# hail.net
KiCad netlist of a schematic drawn in EAGLE
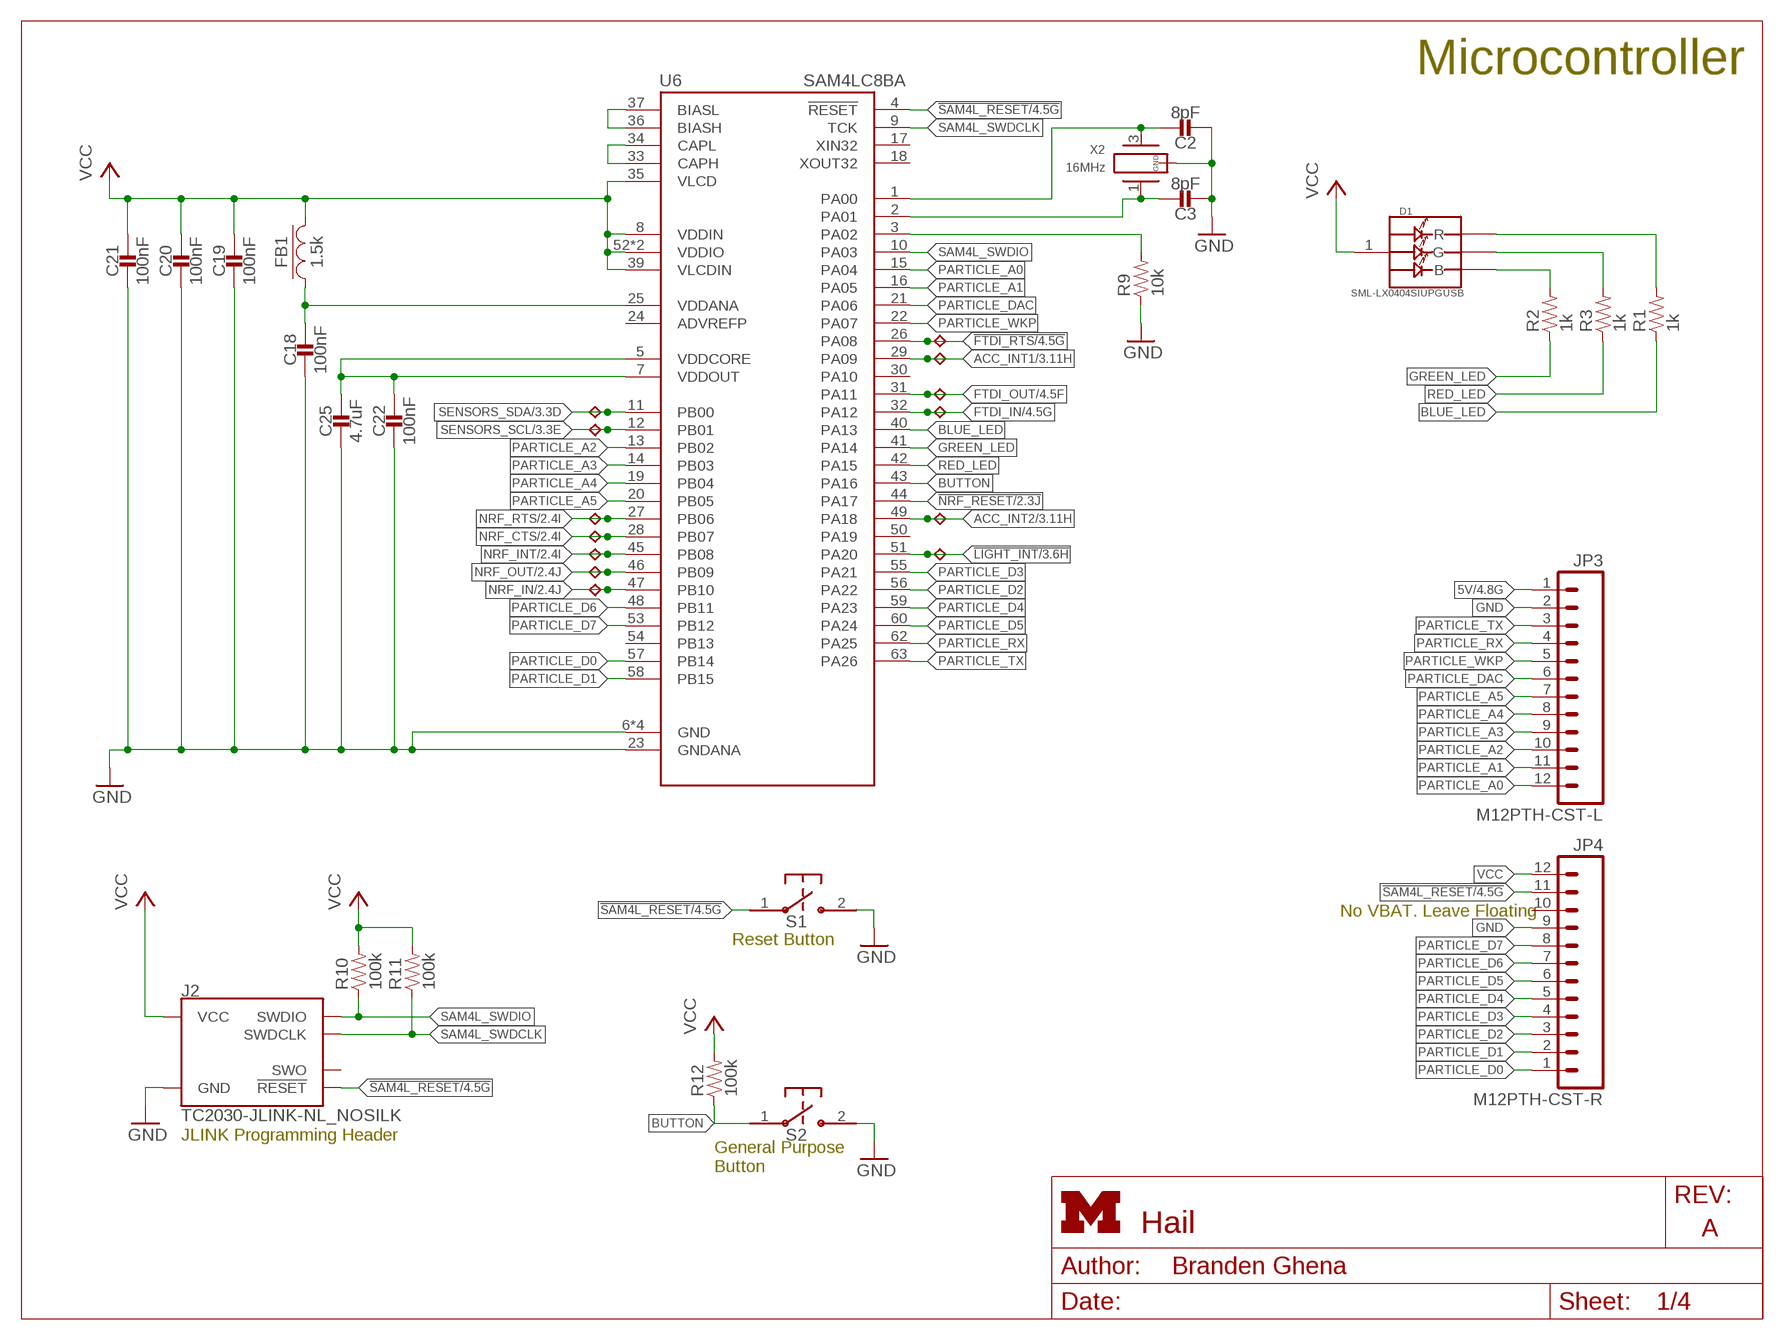
[diagram p0: schematic, sheet 1]
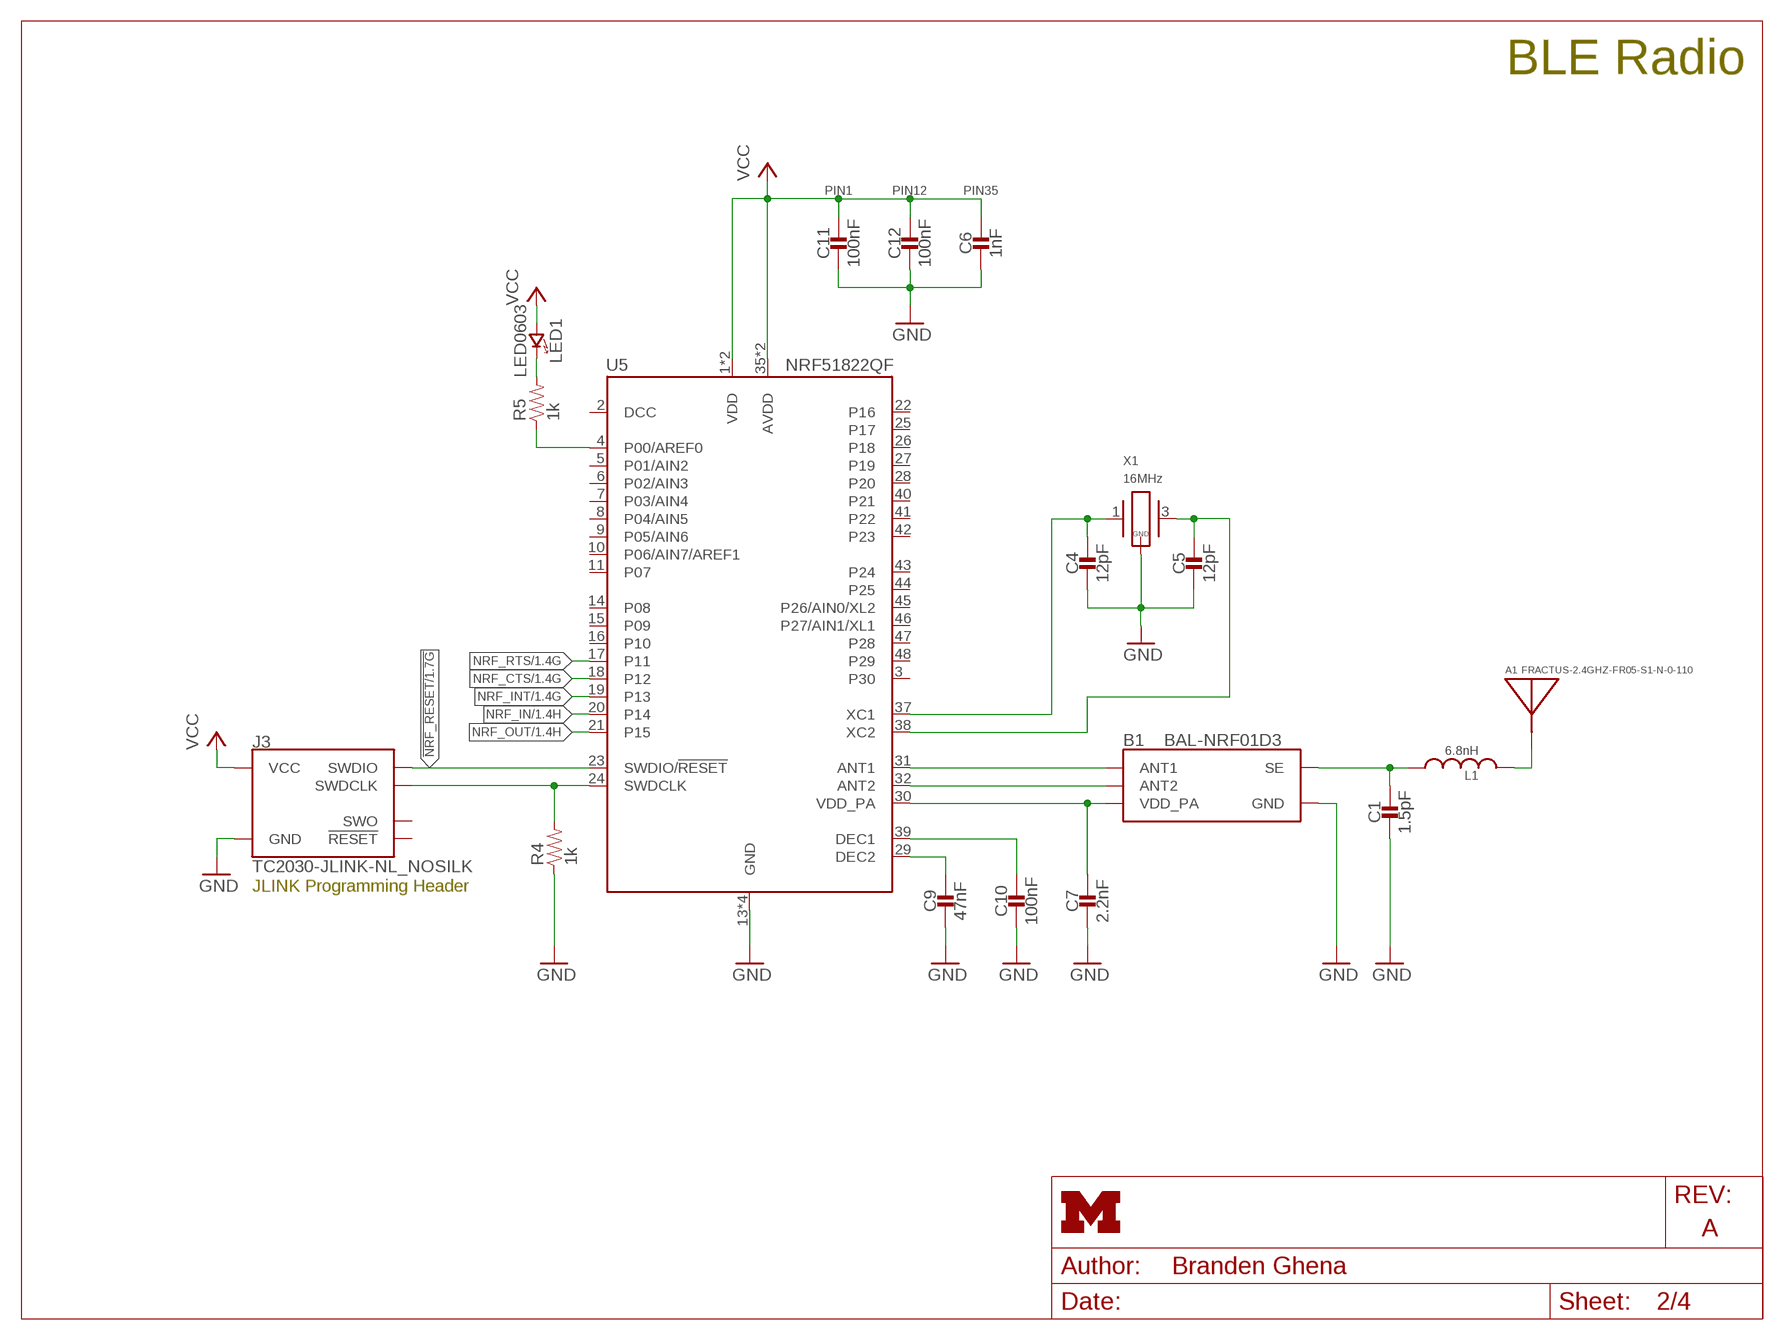
[diagram p1: schematic, sheet 2]
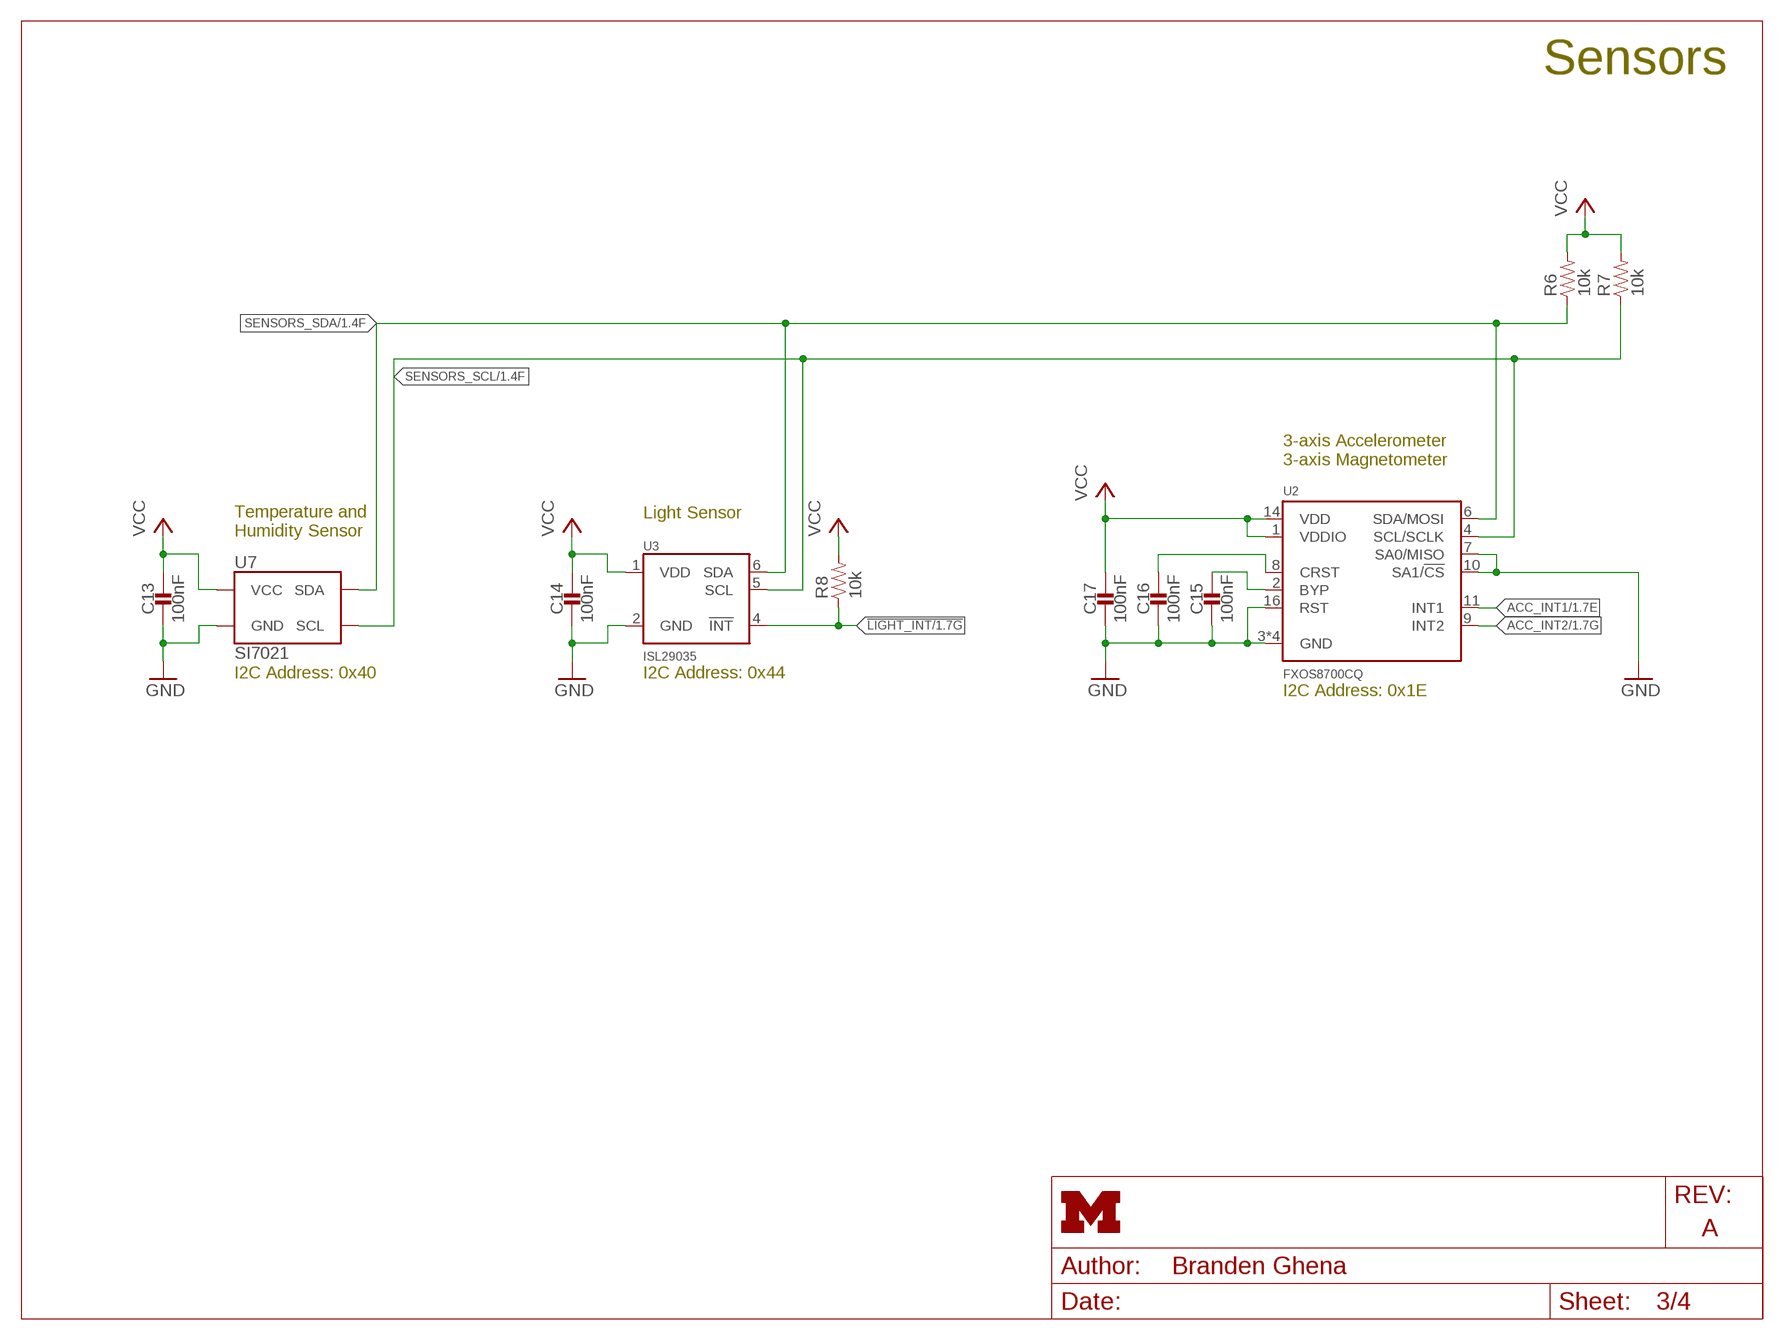
[diagram p2: schematic, sheet 3]
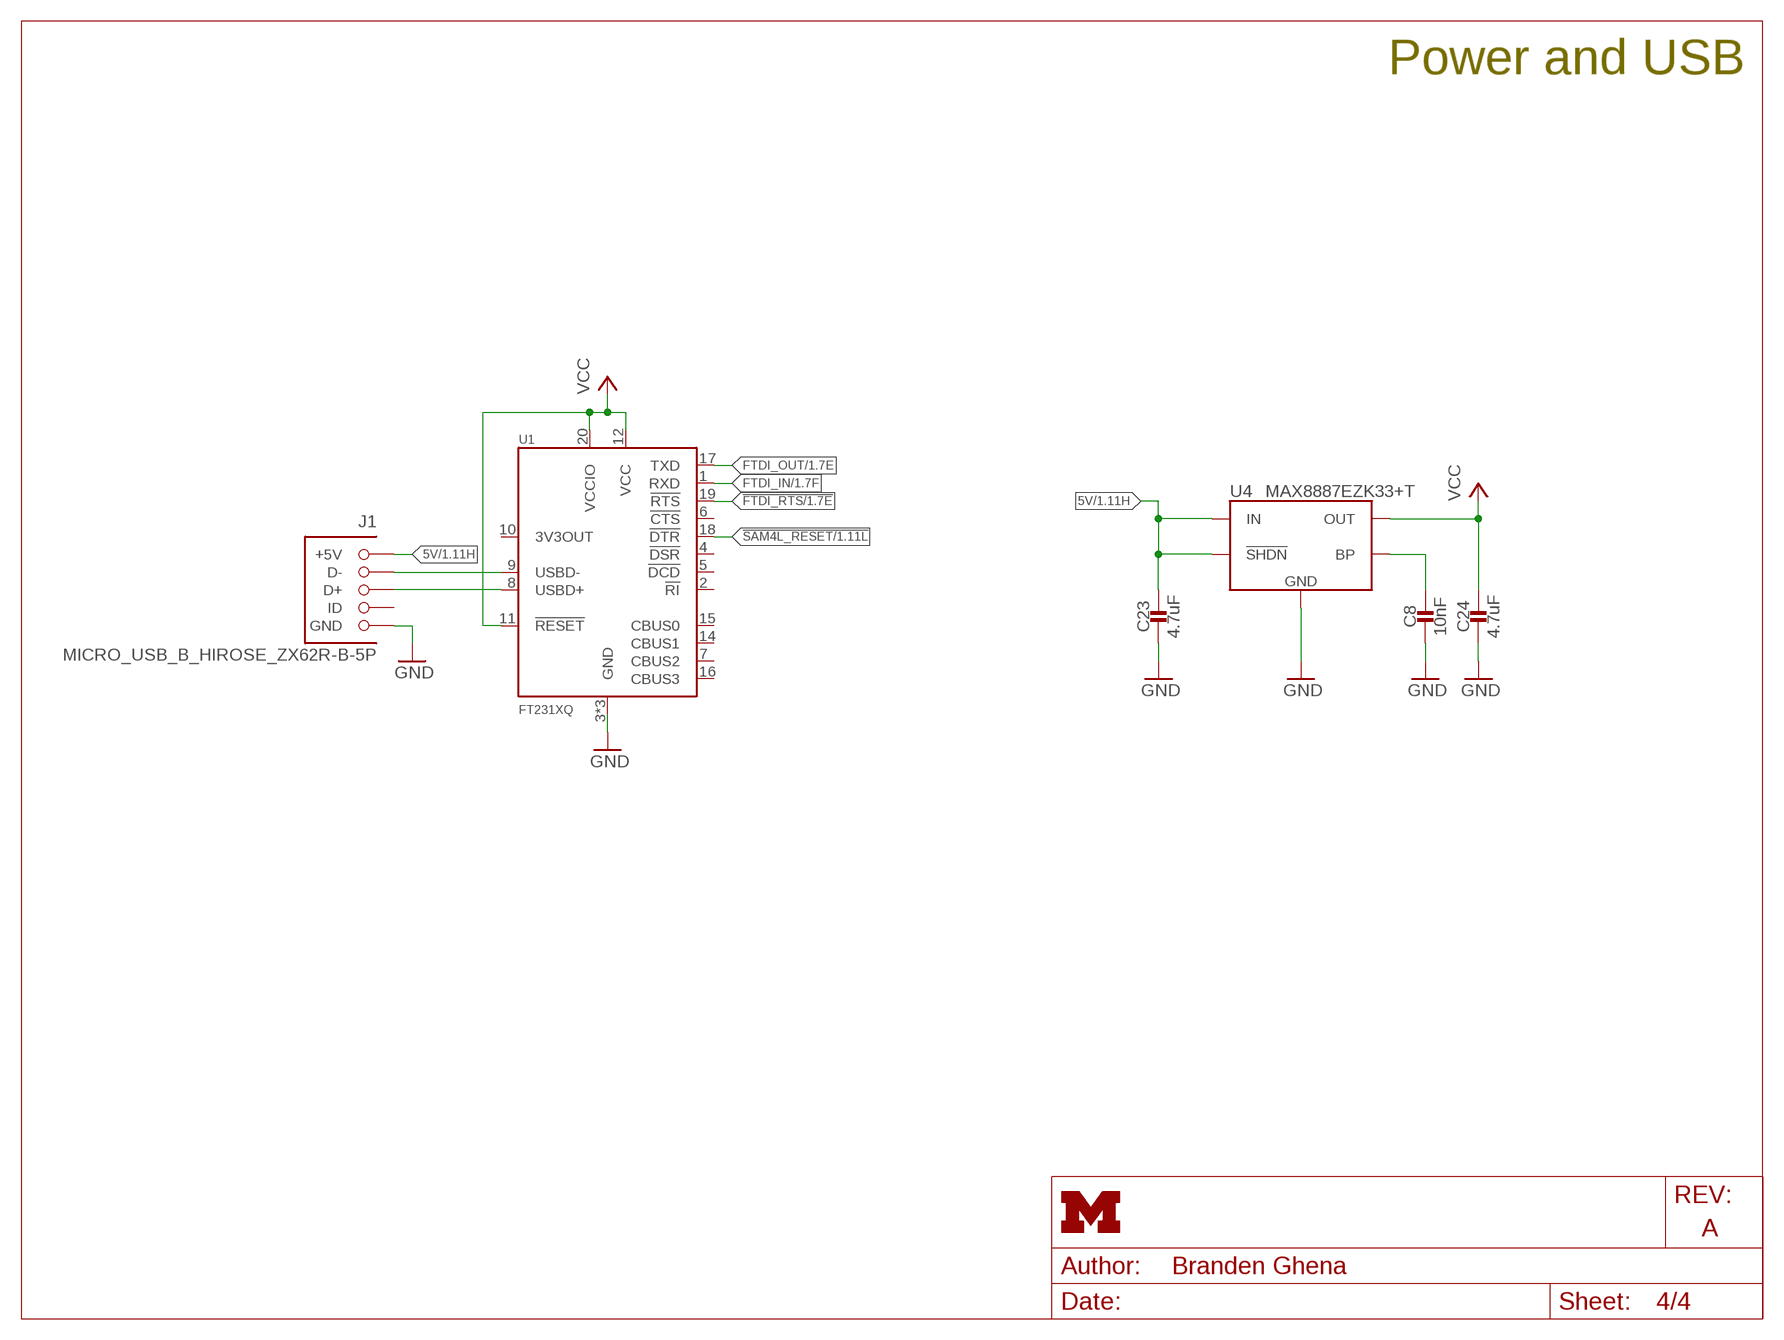
[diagram p3: schematic, sheet 4]

(export (version "E")
  (design (tool "Eeschema 10.0.6"))
  (components
    (comp (ref "A1")
      (value "FRACTUS-2.4GHZ-FR05-S1-N-0-110")
      (footprint "eagle-import:FRACTUS-ANTENNA-FR05-S1-N-0-110")
      (libsource (lib "eagle-import") (part "FRACTUS-2.4GHZ-FR05-S1-N-0-110"))
    )
    (comp (ref "B1")
      (value "BAL-NRF01D3")
      (footprint "eagle-import:BAL-NRF01D3")
      (libsource (lib "eagle-import") (part "BAL-NRF01D3"))
    )
    (comp (ref "C1")
      (value "1.5pF")
      (footprint "eagle-import:0402_CAP")
      (libsource (lib "eagle-import") (part "CAPACITOR0402_CAP"))
    )
    (comp (ref "C4")
      (value "12pF")
      (footprint "eagle-import:0402_CAP")
      (libsource (lib "eagle-import") (part "CAPACITOR0402_CAP"))
    )
    (comp (ref "C5")
      (value "12pF")
      (footprint "eagle-import:0402_CAP")
      (libsource (lib "eagle-import") (part "CAPACITOR0402_CAP"))
    )
    (comp (ref "C6")
      (value "1nF")
      (footprint "eagle-import:0402_CAP")
      (libsource (lib "eagle-import") (part "CAPACITOR0402_CAP"))
    )
    (comp (ref "C7")
      (value "2.2nF")
      (footprint "eagle-import:0402_CAP")
      (libsource (lib "eagle-import") (part "CAPACITOR0402_CAP"))
    )
    (comp (ref "C9")
      (value "47nF")
      (footprint "eagle-import:0402_CAP")
      (libsource (lib "eagle-import") (part "CAPACITOR0402_CAP"))
    )
    (comp (ref "C10")
      (value "100nF")
      (footprint "eagle-import:0402_CAP")
      (libsource (lib "eagle-import") (part "CAPACITOR0402_CAP"))
    )
    (comp (ref "C11")
      (value "100nF")
      (footprint "eagle-import:0402_CAP")
      (libsource (lib "eagle-import") (part "CAPACITOR0402_CAP"))
    )
    (comp (ref "C12")
      (value "100nF")
      (footprint "eagle-import:0402_CAP")
      (libsource (lib "eagle-import") (part "CAPACITOR0402_CAP"))
    )
    (comp (ref "J3")
      (value "TC2030-JLINK-NL_NOSILK")
      (footprint "eagle-import:TC2030-IDC-NL_NOSILK")
      (libsource (lib "eagle-import") (part "TC2030-JLINK-NL_NOSILK"))
    )
    (comp (ref "L1")
      (value "6.8nH")
      (footprint "eagle-import:0402_CAP")
      (libsource (lib "eagle-import") (part "INDUCTOR0402"))
    )
    (comp (ref "LED1")
      (value "LED0603")
      (footprint "eagle-import:LED-0603")
      (libsource (lib "eagle-import") (part "LED0603"))
    )
    (comp (ref "R4")
      (value "1k")
      (footprint "eagle-import:0402_RES")
      (libsource (lib "eagle-import") (part "RESISTOR0402_RES"))
    )
    (comp (ref "R5")
      (value "1k")
      (footprint "eagle-import:0402_RES")
      (libsource (lib "eagle-import") (part "RESISTOR0402_RES"))
    )
    (comp (ref "U5")
      (value "NRF51822QF")
      (footprint "eagle-import:QFN-48-6MM")
      (fields (field (name "DIGIKEY") "1490-1049-1-ND"))
      (libsource (lib "eagle-import") (part "NRF51822QF"))
    )
    (comp (ref "X1")
      (value "16MHz")
      (footprint "eagle-import:TXC-8Y")
      (libsource (lib "eagle-import") (part "TXC-8Y"))
    )
    (comp (ref "C8")
      (value "10nF")
      (footprint "eagle-import:0402_CAP")
      (libsource (lib "eagle-import") (part "CAPACITOR0402_CAP"))
    )
    (comp (ref "C23")
      (value "4.7uF")
      (footprint "eagle-import:0402_CAP")
      (libsource (lib "eagle-import") (part "CAPACITOR0402_CAP"))
    )
    (comp (ref "C24")
      (value "4.7uF")
      (footprint "eagle-import:0402_CAP")
      (libsource (lib "eagle-import") (part "CAPACITOR0402_CAP"))
    )
    (comp (ref "J1")
      (value "MICRO_USB_B_HIROSE_ZX62R-B-5P")
      (footprint "eagle-import:USB_MICRO_B-HIROSE-ZX62R-B-5P")
      (fields (field (name "DIGIKEY") "H125274CT-ND"))
      (libsource (lib "eagle-import") (part "MICRO_USB_B_HIROSE_ZX62R-B-5P"))
    )
    (comp (ref "U1")
      (value "FT231XQ")
      (footprint "eagle-import:QFN-20-4MM")
      (fields (field (name "MPN") "FT231XQ-R"))
      (libsource (lib "eagle-import") (part "FT231XQ"))
    )
    (comp (ref "U4")
      (value "MAX8887EZK33+T")
      (footprint "eagle-import:SOT-23-5")
      (libsource (lib "eagle-import") (part "MAX8887EZK33+T"))
    )
    (comp (ref "C2")
      (value "8pF")
      (footprint "eagle-import:0402_CAP")
      (libsource (lib "eagle-import") (part "CAPACITOR0402_CAP"))
    )
    (comp (ref "C3")
      (value "8pF")
      (footprint "eagle-import:0402_CAP")
      (libsource (lib "eagle-import") (part "CAPACITOR0402_CAP"))
    )
    (comp (ref "C18")
      (value "100nF")
      (footprint "eagle-import:0402_CAP")
      (libsource (lib "eagle-import") (part "CAPACITOR0402_CAP"))
    )
    (comp (ref "C19")
      (value "100nF")
      (footprint "eagle-import:0402_CAP")
      (libsource (lib "eagle-import") (part "CAPACITOR0402_CAP"))
    )
    (comp (ref "C20")
      (value "100nF")
      (footprint "eagle-import:0402_CAP")
      (libsource (lib "eagle-import") (part "CAPACITOR0402_CAP"))
    )
    (comp (ref "C21")
      (value "100nF")
      (footprint "eagle-import:0402_CAP")
      (libsource (lib "eagle-import") (part "CAPACITOR0402_CAP"))
    )
    (comp (ref "C22")
      (value "100nF")
      (footprint "eagle-import:0402_CAP")
      (libsource (lib "eagle-import") (part "CAPACITOR0402_CAP"))
    )
    (comp (ref "C25")
      (value "4.7uF")
      (footprint "eagle-import:0402_CAP")
      (libsource (lib "eagle-import") (part "CAPACITOR0402_CAP"))
    )
    (comp (ref "D1")
      (value "SML-LX0404SIUPGUSB")
      (footprint "eagle-import:1MM_SQ_4PAD")
      (libsource (lib "eagle-import") (part "SML-LX0404SIUPGUSB"))
    )
    (comp (ref "FB1")
      (value "1.5k")
      (footprint "eagle-import:0402_CAP")
      (libsource (lib "eagle-import") (part "FERRITE_BEAD0402"))
    )
    (comp (ref "J2")
      (value "TC2030-JLINK-NL_NOSILK")
      (footprint "eagle-import:TC2030-IDC-NL_NOSILK")
      (libsource (lib "eagle-import") (part "TC2030-JLINK-NL_NOSILK"))
    )
    (comp (ref "JP3")
      (value "M12PTH-CST-L")
      (footprint "eagle-import:1X12-CASTELLATED")
      (libsource (lib "eagle-import") (part "M12PTH-CST-L"))
    )
    (comp (ref "JP4")
      (value "M12PTH-CST-R")
      (footprint "eagle-import:1X12-CASTELLATED")
      (libsource (lib "eagle-import") (part "M12PTH-CST-R"))
    )
    (comp (ref "R1")
      (value "1k")
      (footprint "eagle-import:0402_RES")
      (libsource (lib "eagle-import") (part "RESISTOR0402_RES"))
    )
    (comp (ref "R2")
      (value "1k")
      (footprint "eagle-import:0402_RES")
      (libsource (lib "eagle-import") (part "RESISTOR0402_RES"))
    )
    (comp (ref "R3")
      (value "1k")
      (footprint "eagle-import:0402_RES")
      (libsource (lib "eagle-import") (part "RESISTOR0402_RES"))
    )
    (comp (ref "R9")
      (value "10k")
      (footprint "eagle-import:0402_RES")
      (libsource (lib "eagle-import") (part "RESISTOR0402_RES"))
    )
    (comp (ref "R10")
      (value "100k")
      (footprint "eagle-import:0402_RES")
      (libsource (lib "eagle-import") (part "RESISTOR0402_RES"))
    )
    (comp (ref "R11")
      (value "100k")
      (footprint "eagle-import:0402_RES")
      (libsource (lib "eagle-import") (part "RESISTOR0402_RES"))
    )
    (comp (ref "R12")
      (value "100k")
      (footprint "eagle-import:0402_RES")
      (libsource (lib "eagle-import") (part "RESISTOR0402_RES"))
    )
    (comp (ref "S1")
      (value "B3U-1000P")
      (footprint "eagle-import:B3U-1000P")
      (libsource (lib "eagle-import") (part "B3U-1000P"))
    )
    (comp (ref "S2")
      (value "B3U-1000P")
      (footprint "eagle-import:B3U-1000P")
      (libsource (lib "eagle-import") (part "B3U-1000P"))
    )
    (comp (ref "TP1")
      (value "TPB1,27")
      (footprint "eagle-import:B1,27")
      (libsource (lib "eagle-import") (part "TPB1,27"))
    )
    (comp (ref "TP2")
      (value "TPB1,27")
      (footprint "eagle-import:B1,27")
      (libsource (lib "eagle-import") (part "TPB1,27"))
    )
    (comp (ref "TP3")
      (value "TPB1,27")
      (footprint "eagle-import:B1,27")
      (libsource (lib "eagle-import") (part "TPB1,27"))
    )
    (comp (ref "TP4")
      (value "TPB1,27")
      (footprint "eagle-import:B1,27")
      (libsource (lib "eagle-import") (part "TPB1,27"))
    )
    (comp (ref "TP5")
      (value "TPB1,27")
      (footprint "eagle-import:B1,27")
      (libsource (lib "eagle-import") (part "TPB1,27"))
    )
    (comp (ref "TP6")
      (value "TPB1,27")
      (footprint "eagle-import:B1,27")
      (libsource (lib "eagle-import") (part "TPB1,27"))
    )
    (comp (ref "TP7")
      (value "TPB1,27")
      (footprint "eagle-import:B1,27")
      (libsource (lib "eagle-import") (part "TPB1,27"))
    )
    (comp (ref "TP8")
      (value "TPB1,27")
      (footprint "eagle-import:B1,27")
      (libsource (lib "eagle-import") (part "TPB1,27"))
    )
    (comp (ref "TP9")
      (value "TPB1,27")
      (footprint "eagle-import:B1,27")
      (libsource (lib "eagle-import") (part "TPB1,27"))
    )
    (comp (ref "TP10")
      (value "TPB1,27")
      (footprint "eagle-import:B1,27")
      (libsource (lib "eagle-import") (part "TPB1,27"))
    )
    (comp (ref "TP11")
      (value "TPB1,27")
      (footprint "eagle-import:B1,27")
      (libsource (lib "eagle-import") (part "TPB1,27"))
    )
    (comp (ref "TP12")
      (value "TPB1,27")
      (footprint "eagle-import:B1,27")
      (libsource (lib "eagle-import") (part "TPB1,27"))
    )
    (comp (ref "TP13")
      (value "TPB1,27")
      (footprint "eagle-import:B1,27")
      (libsource (lib "eagle-import") (part "TPB1,27"))
    )
    (comp (ref "U6")
      (value "SAM4LC8BA")
      (footprint "eagle-import:QFN-64-9MM")
      (fields (field (name "DIGIKEY") "ATSAM4LC8BA-MURCT-ND"))
      (libsource (lib "eagle-import") (part "SAM4LC8BA"))
    )
    (comp (ref "X2")
      (value "16MHz")
      (footprint "eagle-import:FHXXX")
      (libsource (lib "eagle-import") (part "FH1600015"))
    )
    (comp (ref "C13")
      (value "100nF")
      (footprint "eagle-import:0402_CAP")
      (libsource (lib "eagle-import") (part "CAPACITOR0402_CAP"))
    )
    (comp (ref "C14")
      (value "100nF")
      (footprint "eagle-import:0402_CAP")
      (libsource (lib "eagle-import") (part "CAPACITOR0402_CAP"))
    )
    (comp (ref "C15")
      (value "100nF")
      (footprint "eagle-import:0402_CAP")
      (libsource (lib "eagle-import") (part "CAPACITOR0402_CAP"))
    )
    (comp (ref "C16")
      (value "100nF")
      (footprint "eagle-import:0402_CAP")
      (libsource (lib "eagle-import") (part "CAPACITOR0402_CAP"))
    )
    (comp (ref "C17")
      (value "100nF")
      (footprint "eagle-import:0402_CAP")
      (libsource (lib "eagle-import") (part "CAPACITOR0402_CAP"))
    )
    (comp (ref "R6")
      (value "10k")
      (footprint "eagle-import:0402_RES")
      (libsource (lib "eagle-import") (part "RESISTOR0402_RES"))
    )
    (comp (ref "R7")
      (value "10k")
      (footprint "eagle-import:0402_RES")
      (libsource (lib "eagle-import") (part "RESISTOR0402_RES"))
    )
    (comp (ref "R8")
      (value "10k")
      (footprint "eagle-import:0402_RES")
      (libsource (lib "eagle-import") (part "RESISTOR0402_RES"))
    )
    (comp (ref "U2")
      (value "FXOS8700CQ")
      (footprint "eagle-import:QFN-16-3MM")
      (fields (field (name "MPN") "FXOS8700CQR1"))
      (libsource (lib "eagle-import") (part "FXOS8700CQ"))
    )
    (comp (ref "U3")
      (value "ISL29035")
      (footprint "eagle-import:ODFN-6-1.5MMX1.6MM")
      (fields (field (name "MPN") "ISL29035IROZ-T7"))
      (libsource (lib "eagle-import") (part "ISL29035"))
    )
    (comp (ref "U7")
      (value "SI7021")
      (footprint "eagle-import:DFN-6_3MM")
      (fields (field (name "DIGIKEY") "336-3141-ND"))
      (libsource (lib "eagle-import") (part "SI7021"))
    )
  )
  (nets
    (net (code "1") (name "5V") (class "Default")
      (node (ref "C23") (pin "1") (pinfunction "1_1") (pintype "bidirectional"))
      (node (ref "J1") (pin "1") (pinfunction "+5V_1") (pintype "bidirectional"))
      (node (ref "JP3") (pin "1") (pinfunction "12_1") (pintype "passive"))
      (node (ref "U4") (pin "1") (pinfunction "IN_1") (pintype "bidirectional"))
      (node (ref "U4") (pin "3") (pinfunction "~{SHDN}_3") (pintype "bidirectional"))
    )
    (net (code "2") (name "ACC_INT1") (class "Default")
      (node (ref "TP8") (pin "TP") (pinfunction "TP_TP") (pintype "input"))
      (node (ref "U2") (pin "11") (pinfunction "INT1_11") (pintype "bidirectional"))
      (node (ref "U6") (pin "29") (pinfunction "PA09_29") (pintype "bidirectional"))
    )
    (net (code "3") (name "ACC_INT2") (class "Default")
      (node (ref "TP9") (pin "TP") (pinfunction "TP_TP") (pintype "input"))
      (node (ref "U2") (pin "9") (pinfunction "INT2_9") (pintype "bidirectional"))
      (node (ref "U6") (pin "49") (pinfunction "PA18_49") (pintype "bidirectional"))
    )
    (net (code "4") (name "ADVREFP") (class "Default")
      (node (ref "U6") (pin "24") (pinfunction "ADVREFP_24") (pintype "power_in"))
    )
    (net (code "5") (name "BLUE_LED") (class "Default")
      (node (ref "R1") (pin "1") (pinfunction "1_1") (pintype "passive"))
      (node (ref "U6") (pin "40") (pinfunction "PA13_40") (pintype "bidirectional"))
    )
    (net (code "6") (name "BUTTON") (class "Default")
      (node (ref "R12") (pin "1") (pinfunction "1_1") (pintype "passive"))
      (node (ref "S2") (pin "1") (pinfunction "P$1_1") (pintype "passive"))
      (node (ref "U6") (pin "43") (pinfunction "PA16_43") (pintype "bidirectional"))
    )
    (net (code "7") (name "FTDI_IN") (class "Default")
      (node (ref "TP13") (pin "TP") (pinfunction "TP_TP") (pintype "input"))
      (node (ref "U1") (pin "1") (pinfunction "RXD_1") (pintype "bidirectional"))
      (node (ref "U6") (pin "32") (pinfunction "PA12_32") (pintype "bidirectional"))
    )
    (net (code "8") (name "FTDI_OUT") (class "Default")
      (node (ref "TP12") (pin "TP") (pinfunction "TP_TP") (pintype "input"))
      (node (ref "U1") (pin "17") (pinfunction "TXD_17") (pintype "bidirectional"))
      (node (ref "U6") (pin "31") (pinfunction "PA11_31") (pintype "bidirectional"))
    )
    (net (code "9") (name "GND") (class "Default")
      (node (ref "B1") (pin "GND") (pinfunction "GND_GND") (pintype "bidirectional"))
      (node (ref "C1") (pin "2") (pinfunction "2_2") (pintype "bidirectional"))
      (node (ref "C10") (pin "2") (pinfunction "2_2") (pintype "bidirectional"))
      (node (ref "C11") (pin "2") (pinfunction "2_2") (pintype "bidirectional"))
      (node (ref "C12") (pin "2") (pinfunction "2_2") (pintype "bidirectional"))
      (node (ref "C13") (pin "2") (pinfunction "2_2") (pintype "bidirectional"))
      (node (ref "C14") (pin "2") (pinfunction "2_2") (pintype "bidirectional"))
      (node (ref "C15") (pin "2") (pinfunction "2_2") (pintype "bidirectional"))
      (node (ref "C16") (pin "2") (pinfunction "2_2") (pintype "bidirectional"))
      (node (ref "C17") (pin "2") (pinfunction "2_2") (pintype "bidirectional"))
      (node (ref "C18") (pin "2") (pinfunction "2_2") (pintype "bidirectional"))
      (node (ref "C19") (pin "2") (pinfunction "2_2") (pintype "bidirectional"))
      (node (ref "C2") (pin "2") (pinfunction "2_2") (pintype "bidirectional"))
      (node (ref "C20") (pin "2") (pinfunction "2_2") (pintype "bidirectional"))
      (node (ref "C21") (pin "2") (pinfunction "2_2") (pintype "bidirectional"))
      (node (ref "C22") (pin "2") (pinfunction "2_2") (pintype "bidirectional"))
      (node (ref "C23") (pin "2") (pinfunction "2_2") (pintype "bidirectional"))
      (node (ref "C24") (pin "2") (pinfunction "2_2") (pintype "bidirectional"))
      (node (ref "C25") (pin "2") (pinfunction "2_2") (pintype "bidirectional"))
      (node (ref "C3") (pin "2") (pinfunction "2_2") (pintype "bidirectional"))
      (node (ref "C4") (pin "2") (pinfunction "2_2") (pintype "bidirectional"))
      (node (ref "C5") (pin "2") (pinfunction "2_2") (pintype "bidirectional"))
      (node (ref "C6") (pin "2") (pinfunction "2_2") (pintype "bidirectional"))
      (node (ref "C7") (pin "2") (pinfunction "2_2") (pintype "bidirectional"))
      (node (ref "C8") (pin "2") (pinfunction "2_2") (pintype "bidirectional"))
      (node (ref "C9") (pin "2") (pinfunction "2_2") (pintype "bidirectional"))
      (node (ref "J1") (pin "5") (pinfunction "GND_5") (pintype "bidirectional"))
      (node (ref "J2") (pin "5") (pinfunction "GND_5") (pintype "bidirectional"))
      (node (ref "J3") (pin "5") (pinfunction "GND_5") (pintype "bidirectional"))
      (node (ref "JP3") (pin "2") (pinfunction "11_2") (pintype "passive"))
      (node (ref "JP4") (pin "9") (pinfunction "9_9") (pintype "passive"))
      (node (ref "R4") (pin "1") (pinfunction "1_1") (pintype "passive"))
      (node (ref "R9") (pin "1") (pinfunction "1_1") (pintype "passive"))
      (node (ref "S1") (pin "2") (pinfunction "P$2_2") (pintype "passive"))
      (node (ref "S2") (pin "2") (pinfunction "P$2_2") (pintype "passive"))
      (node (ref "U1") (pin "13") (pinfunction "GND_13") (pintype "bidirectional"))
      (node (ref "U1") (pin "3") (pinfunction "GND_3") (pintype "bidirectional"))
      (node (ref "U1") (pin "GND") (pinfunction "GND_GND") (pintype "bidirectional"))
      (node (ref "U2") (pin "10") (pinfunction "SA1/~{CS}_10") (pintype "bidirectional"))
      (node (ref "U2") (pin "12") (pinfunction "GND_12") (pintype "bidirectional"))
      (node (ref "U2") (pin "13") (pinfunction "GND_13") (pintype "bidirectional"))
      (node (ref "U2") (pin "16") (pinfunction "RST_16") (pintype "bidirectional"))
      (node (ref "U2") (pin "3") (pinfunction "GND_3") (pintype "bidirectional"))
      (node (ref "U2") (pin "5") (pinfunction "GND_5") (pintype "bidirectional"))
      (node (ref "U2") (pin "7") (pinfunction "SA0/MISO_7") (pintype "bidirectional"))
      (node (ref "U3") (pin "2") (pinfunction "GND_2") (pintype "bidirectional"))
      (node (ref "U4") (pin "2") (pinfunction "GND_2") (pintype "bidirectional"))
      (node (ref "U5") (pin "13") (pinfunction "GND_13") (pintype "bidirectional"))
      (node (ref "U5") (pin "33") (pinfunction "GND_33") (pintype "bidirectional"))
      (node (ref "U5") (pin "34") (pinfunction "GND_34") (pintype "bidirectional"))
      (node (ref "U5") (pin "GND") (pinfunction "GND_GND") (pintype "bidirectional"))
      (node (ref "U6") (pin "23") (pinfunction "GNDANA_23") (pintype "power_in"))
      (node (ref "U6") (pin "38") (pinfunction "GND_38") (pintype "power_in"))
      (node (ref "U6") (pin "6") (pinfunction "GND_6") (pintype "power_in"))
      (node (ref "U6") (pin "64") (pinfunction "GND_64") (pintype "power_in"))
      (node (ref "U6") (pin "GND") (pinfunction "GND_GND") (pintype "power_in"))
      (node (ref "U7") (pin "2") (pinfunction "GND_2") (pintype "bidirectional"))
      (node (ref "X1") (pin "2") (pinfunction "GND_2") (pintype "bidirectional"))
      (node (ref "X1") (pin "4") (pinfunction "GND_4") (pintype "bidirectional"))
      (node (ref "X2") (pin "2") (pinfunction "GND_2") (pintype "bidirectional"))
      (node (ref "X2") (pin "4") (pinfunction "GND_4") (pintype "bidirectional"))
    )
    (net (code "10") (name "GREEN_LED") (class "Default")
      (node (ref "R2") (pin "1") (pinfunction "1_1") (pintype "passive"))
      (node (ref "U6") (pin "41") (pinfunction "PA14_41") (pintype "bidirectional"))
    )
    (net (code "11") (name "NRF_CTS") (class "Default")
      (node (ref "TP2") (pin "TP") (pinfunction "TP_TP") (pintype "input"))
      (node (ref "U5") (pin "18") (pinfunction "P12_18") (pintype "bidirectional"))
      (node (ref "U6") (pin "28") (pinfunction "PB07_28") (pintype "bidirectional"))
    )
    (net (code "12") (name "NRF_IN") (class "Default")
      (node (ref "TP5") (pin "TP") (pinfunction "TP_TP") (pintype "input"))
      (node (ref "U5") (pin "20") (pinfunction "P14_20") (pintype "bidirectional"))
      (node (ref "U6") (pin "47") (pinfunction "PB10_47") (pintype "bidirectional"))
    )
    (net (code "13") (name "NRF_INT") (class "Default")
      (node (ref "TP3") (pin "TP") (pinfunction "TP_TP") (pintype "input"))
      (node (ref "U5") (pin "19") (pinfunction "P13_19") (pintype "bidirectional"))
      (node (ref "U6") (pin "45") (pinfunction "PB08_45") (pintype "bidirectional"))
    )
    (net (code "14") (name "NRF_OUT") (class "Default")
      (node (ref "TP4") (pin "TP") (pinfunction "TP_TP") (pintype "input"))
      (node (ref "U5") (pin "21") (pinfunction "P15_21") (pintype "bidirectional"))
      (node (ref "U6") (pin "46") (pinfunction "PB09_46") (pintype "bidirectional"))
    )
    (net (code "15") (name "NRF_RTS") (class "Default")
      (node (ref "TP1") (pin "TP") (pinfunction "TP_TP") (pintype "input"))
      (node (ref "U5") (pin "17") (pinfunction "P11_17") (pintype "bidirectional"))
      (node (ref "U6") (pin "27") (pinfunction "PB06_27") (pintype "bidirectional"))
    )
    (net (code "16") (name "Net-(A1-ANTENNA)") (class "Default")
      (node (ref "A1") (pin "ANT") (pinfunction "ANTENNA_ANT") (pintype "bidirectional"))
      (node (ref "L1") (pin "2") (pinfunction "2_2") (pintype "bidirectional"))
    )
    (net (code "17") (name "Net-(B1-PadSE)") (class "Default")
      (node (ref "B1") (pin "SE") (pinfunction "SE_SE") (pintype "bidirectional"))
      (node (ref "C1") (pin "1") (pinfunction "1_1") (pintype "bidirectional"))
      (node (ref "L1") (pin "1") (pinfunction "1_1") (pintype "bidirectional"))
    )
    (net (code "18") (name "Net-(B1-VDD_PA)") (class "Default")
      (node (ref "B1") (pin "VCC") (pinfunction "VDD_PA_VCC") (pintype "bidirectional"))
      (node (ref "C7") (pin "1") (pinfunction "1_1") (pintype "bidirectional"))
      (node (ref "U5") (pin "30") (pinfunction "VDD_PA_30") (pintype "bidirectional"))
    )
    (net (code "19") (name "Net-(D1-B)") (class "Default")
      (node (ref "D1") (pin "3") (pinfunction "B_3") (pintype "output"))
      (node (ref "R2") (pin "2") (pinfunction "2_2") (pintype "passive"))
    )
    (net (code "20") (name "Net-(D1-G)") (class "Default")
      (node (ref "D1") (pin "4") (pinfunction "G_4") (pintype "output"))
      (node (ref "R3") (pin "2") (pinfunction "2_2") (pintype "passive"))
    )
    (net (code "21") (name "Net-(D1-R)") (class "Default")
      (node (ref "D1") (pin "2") (pinfunction "R_2") (pintype "output"))
      (node (ref "R1") (pin "2") (pinfunction "2_2") (pintype "passive"))
    )
    (net (code "22") (name "Net-(FB1-P$1)") (class "Default")
      (node (ref "C18") (pin "1") (pinfunction "1_1") (pintype "bidirectional"))
      (node (ref "FB1") (pin "1") (pinfunction "P$1_1") (pintype "bidirectional"))
      (node (ref "U6") (pin "25") (pinfunction "VDDANA_25") (pintype "power_in"))
    )
    (net (code "23") (name "Net-(J1-D+)") (class "Default")
      (node (ref "J1") (pin "3") (pinfunction "D+_3") (pintype "bidirectional"))
      (node (ref "U1") (pin "8") (pinfunction "USBD+_8") (pintype "bidirectional"))
    )
    (net (code "24") (name "Net-(J1-D-)") (class "Default")
      (node (ref "J1") (pin "2") (pinfunction "D-_2") (pintype "bidirectional"))
      (node (ref "U1") (pin "9") (pinfunction "USBD-_9") (pintype "bidirectional"))
    )
    (net (code "25") (name "Net-(J3-SWDCLK)") (class "Default")
      (node (ref "J3") (pin "4") (pinfunction "SWDCLK_4") (pintype "bidirectional"))
      (node (ref "R4") (pin "2") (pinfunction "2_2") (pintype "passive"))
      (node (ref "U5") (pin "24") (pinfunction "SWDCLK_24") (pintype "bidirectional"))
    )
    (net (code "26") (name "Net-(LED1-CATHODE)") (class "Default")
      (node (ref "LED1") (pin "C") (pinfunction "CATHODE_C") (pintype "bidirectional"))
      (node (ref "R5") (pin "2") (pinfunction "2_2") (pintype "passive"))
    )
    (net (code "27") (name "Net-(U2-BYP)") (class "Default")
      (node (ref "C15") (pin "1") (pinfunction "1_1") (pintype "bidirectional"))
      (node (ref "U2") (pin "2") (pinfunction "BYP_2") (pintype "bidirectional"))
    )
    (net (code "28") (name "Net-(U2-CRST)") (class "Default")
      (node (ref "C16") (pin "1") (pinfunction "1_1") (pintype "bidirectional"))
      (node (ref "U2") (pin "8") (pinfunction "CRST_8") (pintype "bidirectional"))
    )
    (net (code "29") (name "Net-(U4-BP)") (class "Default")
      (node (ref "C8") (pin "1") (pinfunction "1_1") (pintype "bidirectional"))
      (node (ref "U4") (pin "4") (pinfunction "BP_4") (pintype "bidirectional"))
    )
    (net (code "30") (name "Net-(U5-ANT1)") (class "Default")
      (node (ref "B1") (pin "ANT1") (pinfunction "ANT1_ANT1") (pintype "bidirectional"))
      (node (ref "U5") (pin "31") (pinfunction "ANT1_31") (pintype "bidirectional"))
    )
    (net (code "31") (name "Net-(U5-ANT2)") (class "Default")
      (node (ref "B1") (pin "ANT2") (pinfunction "ANT2_ANT2") (pintype "bidirectional"))
      (node (ref "U5") (pin "32") (pinfunction "ANT2_32") (pintype "bidirectional"))
    )
    (net (code "32") (name "Net-(U5-DEC1)") (class "Default")
      (node (ref "C10") (pin "1") (pinfunction "1_1") (pintype "bidirectional"))
      (node (ref "U5") (pin "39") (pinfunction "DEC1_39") (pintype "bidirectional"))
    )
    (net (code "33") (name "Net-(U5-DEC2)") (class "Default")
      (node (ref "C9") (pin "1") (pinfunction "1_1") (pintype "bidirectional"))
      (node (ref "U5") (pin "29") (pinfunction "DEC2_29") (pintype "bidirectional"))
    )
    (net (code "34") (name "Net-(U5-P00{slash}AREF0)") (class "Default")
      (node (ref "R5") (pin "1") (pinfunction "1_1") (pintype "passive"))
      (node (ref "U5") (pin "4") (pinfunction "P00/AREF0_4") (pintype "bidirectional"))
    )
    (net (code "35") (name "Net-(U5-XC1)") (class "Default")
      (node (ref "C4") (pin "1") (pinfunction "1_1") (pintype "bidirectional"))
      (node (ref "U5") (pin "37") (pinfunction "XC1_37") (pintype "bidirectional"))
      (node (ref "X1") (pin "1") (pinfunction "1_1") (pintype "bidirectional"))
    )
    (net (code "36") (name "Net-(U5-XC2)") (class "Default")
      (node (ref "C5") (pin "1") (pinfunction "1_1") (pintype "bidirectional"))
      (node (ref "U5") (pin "38") (pinfunction "XC2_38") (pintype "bidirectional"))
      (node (ref "X1") (pin "3") (pinfunction "2_3") (pintype "bidirectional"))
    )
    (net (code "37") (name "Net-(U6-BIASH)") (class "Default")
      (node (ref "U6") (pin "36") (pinfunction "BIASH_36") (pintype "bidirectional"))
      (node (ref "U6") (pin "37") (pinfunction "BIASL_37") (pintype "bidirectional"))
    )
    (net (code "38") (name "Net-(U6-CAPH)") (class "Default")
      (node (ref "U6") (pin "33") (pinfunction "CAPH_33") (pintype "bidirectional"))
      (node (ref "U6") (pin "34") (pinfunction "CAPL_34") (pintype "bidirectional"))
    )
    (net (code "39") (name "Net-(U6-PA00)") (class "Default")
      (node (ref "C2") (pin "1") (pinfunction "1_1") (pintype "bidirectional"))
      (node (ref "U6") (pin "1") (pinfunction "PA00_1") (pintype "bidirectional"))
      (node (ref "X2") (pin "3") (pinfunction "2_3") (pintype "bidirectional"))
    )
    (net (code "40") (name "Net-(U6-PA01)") (class "Default")
      (node (ref "C3") (pin "1") (pinfunction "1_1") (pintype "bidirectional"))
      (node (ref "U6") (pin "2") (pinfunction "PA01_2") (pintype "bidirectional"))
      (node (ref "X2") (pin "1") (pinfunction "1_1") (pintype "bidirectional"))
    )
    (net (code "41") (name "Net-(U6-PA02)") (class "Default")
      (node (ref "R9") (pin "2") (pinfunction "2_2") (pintype "passive"))
      (node (ref "U6") (pin "3") (pinfunction "PA02_3") (pintype "bidirectional"))
    )
    (net (code "42") (name "Net-(U6-VDDCORE)") (class "Default")
      (node (ref "C22") (pin "1") (pinfunction "1_1") (pintype "bidirectional"))
      (node (ref "C25") (pin "1") (pinfunction "1_1") (pintype "bidirectional"))
      (node (ref "U6") (pin "5") (pinfunction "VDDCORE_5") (pintype "power_in"))
      (node (ref "U6") (pin "7") (pinfunction "VDDOUT_7") (pintype "power_in"))
    )
    (net (code "43") (name "PARTICLE_A0") (class "Default")
      (node (ref "JP3") (pin "12") (pinfunction "1_12") (pintype "passive"))
      (node (ref "U6") (pin "15") (pinfunction "PA04_15") (pintype "bidirectional"))
    )
    (net (code "44") (name "PARTICLE_A1") (class "Default")
      (node (ref "JP3") (pin "11") (pinfunction "2_11") (pintype "passive"))
      (node (ref "U6") (pin "16") (pinfunction "PA05_16") (pintype "bidirectional"))
    )
    (net (code "45") (name "PARTICLE_A2") (class "Default")
      (node (ref "JP3") (pin "10") (pinfunction "3_10") (pintype "passive"))
      (node (ref "U6") (pin "13") (pinfunction "PB02_13") (pintype "bidirectional"))
    )
    (net (code "46") (name "PARTICLE_A3") (class "Default")
      (node (ref "JP3") (pin "9") (pinfunction "4_9") (pintype "passive"))
      (node (ref "U6") (pin "14") (pinfunction "PB03_14") (pintype "bidirectional"))
    )
    (net (code "47") (name "PARTICLE_A4") (class "Default")
      (node (ref "JP3") (pin "8") (pinfunction "5_8") (pintype "passive"))
      (node (ref "U6") (pin "19") (pinfunction "PB04_19") (pintype "bidirectional"))
    )
    (net (code "48") (name "PARTICLE_A5") (class "Default")
      (node (ref "JP3") (pin "7") (pinfunction "6_7") (pintype "passive"))
      (node (ref "U6") (pin "20") (pinfunction "PB05_20") (pintype "bidirectional"))
    )
    (net (code "49") (name "PARTICLE_D0") (class "Default")
      (node (ref "JP4") (pin "1") (pinfunction "1_1") (pintype "passive"))
      (node (ref "U6") (pin "57") (pinfunction "PB14_57") (pintype "bidirectional"))
    )
    (net (code "50") (name "PARTICLE_D1") (class "Default")
      (node (ref "JP4") (pin "2") (pinfunction "2_2") (pintype "passive"))
      (node (ref "U6") (pin "58") (pinfunction "PB15_58") (pintype "bidirectional"))
    )
    (net (code "51") (name "PARTICLE_D2") (class "Default")
      (node (ref "JP4") (pin "3") (pinfunction "3_3") (pintype "passive"))
      (node (ref "U6") (pin "56") (pinfunction "PA22_56") (pintype "bidirectional"))
    )
    (net (code "52") (name "PARTICLE_D3") (class "Default")
      (node (ref "JP4") (pin "4") (pinfunction "4_4") (pintype "passive"))
      (node (ref "U6") (pin "55") (pinfunction "PA21_55") (pintype "bidirectional"))
    )
    (net (code "53") (name "PARTICLE_D4") (class "Default")
      (node (ref "JP4") (pin "5") (pinfunction "5_5") (pintype "passive"))
      (node (ref "U6") (pin "59") (pinfunction "PA23_59") (pintype "bidirectional"))
    )
    (net (code "54") (name "PARTICLE_D5") (class "Default")
      (node (ref "JP4") (pin "6") (pinfunction "6_6") (pintype "passive"))
      (node (ref "U6") (pin "60") (pinfunction "PA24_60") (pintype "bidirectional"))
    )
    (net (code "55") (name "PARTICLE_D6") (class "Default")
      (node (ref "JP4") (pin "7") (pinfunction "7_7") (pintype "passive"))
      (node (ref "U6") (pin "48") (pinfunction "PB11_48") (pintype "bidirectional"))
    )
    (net (code "56") (name "PARTICLE_D7") (class "Default")
      (node (ref "JP4") (pin "8") (pinfunction "8_8") (pintype "passive"))
      (node (ref "U6") (pin "53") (pinfunction "PB12_53") (pintype "bidirectional"))
    )
    (net (code "57") (name "PARTICLE_DAC") (class "Default")
      (node (ref "JP3") (pin "6") (pinfunction "7_6") (pintype "passive"))
      (node (ref "U6") (pin "21") (pinfunction "PA06_21") (pintype "bidirectional"))
    )
    (net (code "58") (name "PARTICLE_RX") (class "Default")
      (node (ref "JP3") (pin "4") (pinfunction "9_4") (pintype "passive"))
      (node (ref "U6") (pin "62") (pinfunction "PA25_62") (pintype "bidirectional"))
    )
    (net (code "59") (name "PARTICLE_TX") (class "Default")
      (node (ref "JP3") (pin "3") (pinfunction "10_3") (pintype "passive"))
      (node (ref "U6") (pin "63") (pinfunction "PA26_63") (pintype "bidirectional"))
    )
    (net (code "60") (name "PARTICLE_WKP") (class "Default")
      (node (ref "JP3") (pin "5") (pinfunction "8_5") (pintype "passive"))
      (node (ref "U6") (pin "22") (pinfunction "PA07_22") (pintype "bidirectional"))
    )
    (net (code "61") (name "RED_LED") (class "Default")
      (node (ref "R3") (pin "1") (pinfunction "1_1") (pintype "passive"))
      (node (ref "U6") (pin "42") (pinfunction "PA15_42") (pintype "bidirectional"))
    )
    (net (code "62") (name "SAM4L_SWDCLK") (class "Default")
      (node (ref "J2") (pin "4") (pinfunction "SWDCLK_4") (pintype "bidirectional"))
      (node (ref "R11") (pin "1") (pinfunction "1_1") (pintype "passive"))
      (node (ref "U6") (pin "9") (pinfunction "TCK_9") (pintype "bidirectional"))
    )
    (net (code "63") (name "SAM4L_SWDIO") (class "Default")
      (node (ref "J2") (pin "2") (pinfunction "SWDIO_2") (pintype "bidirectional"))
      (node (ref "R10") (pin "1") (pinfunction "1_1") (pintype "passive"))
      (node (ref "U6") (pin "10") (pinfunction "PA03_10") (pintype "bidirectional"))
    )
    (net (code "64") (name "SENSORS_SCL") (class "Default")
      (node (ref "R7") (pin "1") (pinfunction "1_1") (pintype "passive"))
      (node (ref "TP7") (pin "TP") (pinfunction "TP_TP") (pintype "input"))
      (node (ref "U2") (pin "4") (pinfunction "SCL/SCLK_4") (pintype "bidirectional"))
      (node (ref "U3") (pin "5") (pinfunction "SCL_5") (pintype "bidirectional"))
      (node (ref "U6") (pin "12") (pinfunction "PB01_12") (pintype "bidirectional"))
      (node (ref "U7") (pin "6") (pinfunction "SCL_6") (pintype "bidirectional"))
    )
    (net (code "65") (name "SENSORS_SDA") (class "Default")
      (node (ref "R6") (pin "1") (pinfunction "1_1") (pintype "passive"))
      (node (ref "TP6") (pin "TP") (pinfunction "TP_TP") (pintype "input"))
      (node (ref "U2") (pin "6") (pinfunction "SDA/MOSI_6") (pintype "bidirectional"))
      (node (ref "U3") (pin "6") (pinfunction "SDA_6") (pintype "bidirectional"))
      (node (ref "U6") (pin "11") (pinfunction "PB00_11") (pintype "bidirectional"))
      (node (ref "U7") (pin "1") (pinfunction "SDA_1") (pintype "bidirectional"))
    )
    (net (code "66") (name "VCC") (class "Default")
      (node (ref "C11") (pin "1") (pinfunction "1_1") (pintype "bidirectional"))
      (node (ref "C12") (pin "1") (pinfunction "1_1") (pintype "bidirectional"))
      (node (ref "C13") (pin "1") (pinfunction "1_1") (pintype "bidirectional"))
      (node (ref "C14") (pin "1") (pinfunction "1_1") (pintype "bidirectional"))
      (node (ref "C17") (pin "1") (pinfunction "1_1") (pintype "bidirectional"))
      (node (ref "C19") (pin "1") (pinfunction "1_1") (pintype "bidirectional"))
      (node (ref "C20") (pin "1") (pinfunction "1_1") (pintype "bidirectional"))
      (node (ref "C21") (pin "1") (pinfunction "1_1") (pintype "bidirectional"))
      (node (ref "C24") (pin "1") (pinfunction "1_1") (pintype "bidirectional"))
      (node (ref "C6") (pin "1") (pinfunction "1_1") (pintype "bidirectional"))
      (node (ref "D1") (pin "1") (pinfunction "VDD_1") (pintype "bidirectional"))
      (node (ref "FB1") (pin "2") (pinfunction "P$2_2") (pintype "bidirectional"))
      (node (ref "J2") (pin "1") (pinfunction "VCC_1") (pintype "bidirectional"))
      (node (ref "J3") (pin "1") (pinfunction "VCC_1") (pintype "bidirectional"))
      (node (ref "JP4") (pin "12") (pinfunction "12_12") (pintype "passive"))
      (node (ref "LED1") (pin "A") (pinfunction "ANODE_A") (pintype "bidirectional"))
      (node (ref "R10") (pin "2") (pinfunction "2_2") (pintype "passive"))
      (node (ref "R11") (pin "2") (pinfunction "2_2") (pintype "passive"))
      (node (ref "R12") (pin "2") (pinfunction "2_2") (pintype "passive"))
      (node (ref "R6") (pin "2") (pinfunction "2_2") (pintype "passive"))
      (node (ref "R7") (pin "2") (pinfunction "2_2") (pintype "passive"))
      (node (ref "R8") (pin "2") (pinfunction "2_2") (pintype "passive"))
      (node (ref "U1") (pin "11") (pinfunction "~{RESET}_11") (pintype "bidirectional"))
      (node (ref "U1") (pin "12") (pinfunction "VCC_12") (pintype "bidirectional"))
      (node (ref "U1") (pin "20") (pinfunction "VCCIO_20") (pintype "bidirectional"))
      (node (ref "U2") (pin "1") (pinfunction "VDDIO_1") (pintype "bidirectional"))
      (node (ref "U2") (pin "14") (pinfunction "VDD_14") (pintype "bidirectional"))
      (node (ref "U3") (pin "1") (pinfunction "VDD_1") (pintype "bidirectional"))
      (node (ref "U4") (pin "5") (pinfunction "OUT_5") (pintype "bidirectional"))
      (node (ref "U5") (pin "1") (pinfunction "VDD_1") (pintype "bidirectional"))
      (node (ref "U5") (pin "12") (pinfunction "VDD_12") (pintype "bidirectional"))
      (node (ref "U5") (pin "35") (pinfunction "AVDD_35") (pintype "bidirectional"))
      (node (ref "U5") (pin "36") (pinfunction "AVDD_36") (pintype "bidirectional"))
      (node (ref "U6") (pin "35") (pinfunction "VLCD_35") (pintype "bidirectional"))
      (node (ref "U6") (pin "39") (pinfunction "VLCDIN_39") (pintype "power_in"))
      (node (ref "U6") (pin "52") (pinfunction "VDDIO_52") (pintype "power_in"))
      (node (ref "U6") (pin "61") (pinfunction "VDDIO_61") (pintype "power_in"))
      (node (ref "U6") (pin "8") (pinfunction "VDDIN_8") (pintype "power_in"))
      (node (ref "U7") (pin "5") (pinfunction "VCC_5") (pintype "bidirectional"))
    )
    (net (code "67") (name "unconnected-(J1-ID-Pad4)") (class "Default")
      (node (ref "J1") (pin "4") (pinfunction "ID_4") (pintype "bidirectional"))
    )
    (net (code "68") (name "unconnected-(J2-SWO-Pad6)") (class "Default")
      (node (ref "J2") (pin "6") (pinfunction "SWO_6") (pintype "bidirectional"))
    )
    (net (code "69") (name "unconnected-(J3-SWO-Pad6)") (class "Default")
      (node (ref "J3") (pin "6") (pinfunction "SWO_6") (pintype "bidirectional"))
    )
    (net (code "70") (name "unconnected-(J3-~{RESET}-Pad3)") (class "Default")
      (node (ref "J3") (pin "3") (pinfunction "~{RESET}_3") (pintype "bidirectional"))
    )
    (net (code "71") (name "unconnected-(JP4-Pad10)") (class "Default")
      (node (ref "JP4") (pin "10") (pinfunction "10_10") (pintype "passive"))
    )
    (net (code "72") (name "unconnected-(U1-3V3OUT-Pad10)") (class "Default")
      (node (ref "U1") (pin "10") (pinfunction "3V3OUT_10") (pintype "bidirectional"))
    )
    (net (code "73") (name "unconnected-(U1-CBUS0-Pad15)") (class "Default")
      (node (ref "U1") (pin "15") (pinfunction "CBUS0_15") (pintype "bidirectional"))
    )
    (net (code "74") (name "unconnected-(U1-CBUS1-Pad14)") (class "Default")
      (node (ref "U1") (pin "14") (pinfunction "CBUS1_14") (pintype "bidirectional"))
    )
    (net (code "75") (name "unconnected-(U1-CBUS2-Pad7)") (class "Default")
      (node (ref "U1") (pin "7") (pinfunction "CBUS2_7") (pintype "bidirectional"))
    )
    (net (code "76") (name "unconnected-(U1-CBUS3-Pad16)") (class "Default")
      (node (ref "U1") (pin "16") (pinfunction "CBUS3_16") (pintype "bidirectional"))
    )
    (net (code "77") (name "unconnected-(U1-~{CTS}-Pad6)") (class "Default")
      (node (ref "U1") (pin "6") (pinfunction "~{CTS}_6") (pintype "bidirectional"))
    )
    (net (code "78") (name "unconnected-(U1-~{DCD}-Pad5)") (class "Default")
      (node (ref "U1") (pin "5") (pinfunction "~{DCD}_5") (pintype "bidirectional"))
    )
    (net (code "79") (name "unconnected-(U1-~{DSR}-Pad4)") (class "Default")
      (node (ref "U1") (pin "4") (pinfunction "~{DSR}_4") (pintype "bidirectional"))
    )
    (net (code "80") (name "unconnected-(U1-~{RI}-Pad2)") (class "Default")
      (node (ref "U1") (pin "2") (pinfunction "~{RI}_2") (pintype "bidirectional"))
    )
    (net (code "81") (name "unconnected-(U5-DCC-Pad2)") (class "Default")
      (node (ref "U5") (pin "2") (pinfunction "DCC_2") (pintype "bidirectional"))
    )
    (net (code "82") (name "unconnected-(U5-P01{slash}AIN2-Pad5)") (class "Default")
      (node (ref "U5") (pin "5") (pinfunction "P01/AIN2_5") (pintype "bidirectional"))
    )
    (net (code "83") (name "unconnected-(U5-P02{slash}AIN3-Pad6)") (class "Default")
      (node (ref "U5") (pin "6") (pinfunction "P02/AIN3_6") (pintype "bidirectional"))
    )
    (net (code "84") (name "unconnected-(U5-P03{slash}AIN4-Pad7)") (class "Default")
      (node (ref "U5") (pin "7") (pinfunction "P03/AIN4_7") (pintype "bidirectional"))
    )
    (net (code "85") (name "unconnected-(U5-P04{slash}AIN5-Pad8)") (class "Default")
      (node (ref "U5") (pin "8") (pinfunction "P04/AIN5_8") (pintype "bidirectional"))
    )
    (net (code "86") (name "unconnected-(U5-P05{slash}AIN6-Pad9)") (class "Default")
      (node (ref "U5") (pin "9") (pinfunction "P05/AIN6_9") (pintype "bidirectional"))
    )
    (net (code "87") (name "unconnected-(U5-P06{slash}AIN7{slash}AREF1-Pad10)") (class "Default")
      (node (ref "U5") (pin "10") (pinfunction "P06/AIN7/AREF1_10") (pintype "bidirectional"))
    )
    (net (code "88") (name "unconnected-(U5-P07-Pad11)") (class "Default")
      (node (ref "U5") (pin "11") (pinfunction "P07_11") (pintype "bidirectional"))
    )
    (net (code "89") (name "unconnected-(U5-P08-Pad14)") (class "Default")
      (node (ref "U5") (pin "14") (pinfunction "P08_14") (pintype "bidirectional"))
    )
    (net (code "90") (name "unconnected-(U5-P09-Pad15)") (class "Default")
      (node (ref "U5") (pin "15") (pinfunction "P09_15") (pintype "bidirectional"))
    )
    (net (code "91") (name "unconnected-(U5-P10-Pad16)") (class "Default")
      (node (ref "U5") (pin "16") (pinfunction "P10_16") (pintype "bidirectional"))
    )
    (net (code "92") (name "unconnected-(U5-P16-Pad22)") (class "Default")
      (node (ref "U5") (pin "22") (pinfunction "P16_22") (pintype "bidirectional"))
    )
    (net (code "93") (name "unconnected-(U5-P17-Pad25)") (class "Default")
      (node (ref "U5") (pin "25") (pinfunction "P17_25") (pintype "bidirectional"))
    )
    (net (code "94") (name "unconnected-(U5-P18-Pad26)") (class "Default")
      (node (ref "U5") (pin "26") (pinfunction "P18_26") (pintype "bidirectional"))
    )
    (net (code "95") (name "unconnected-(U5-P19-Pad27)") (class "Default")
      (node (ref "U5") (pin "27") (pinfunction "P19_27") (pintype "bidirectional"))
    )
    (net (code "96") (name "unconnected-(U5-P20-Pad28)") (class "Default")
      (node (ref "U5") (pin "28") (pinfunction "P20_28") (pintype "bidirectional"))
    )
    (net (code "97") (name "unconnected-(U5-P21-Pad40)") (class "Default")
      (node (ref "U5") (pin "40") (pinfunction "P21_40") (pintype "bidirectional"))
    )
    (net (code "98") (name "unconnected-(U5-P22-Pad41)") (class "Default")
      (node (ref "U5") (pin "41") (pinfunction "P22_41") (pintype "bidirectional"))
    )
    (net (code "99") (name "unconnected-(U5-P23-Pad42)") (class "Default")
      (node (ref "U5") (pin "42") (pinfunction "P23_42") (pintype "bidirectional"))
    )
    (net (code "100") (name "unconnected-(U5-P24-Pad43)") (class "Default")
      (node (ref "U5") (pin "43") (pinfunction "P24_43") (pintype "bidirectional"))
    )
    (net (code "101") (name "unconnected-(U5-P25-Pad44)") (class "Default")
      (node (ref "U5") (pin "44") (pinfunction "P25_44") (pintype "bidirectional"))
    )
    (net (code "102") (name "unconnected-(U5-P26{slash}AIN0{slash}XL2-Pad45)") (class "Default")
      (node (ref "U5") (pin "45") (pinfunction "P26/AIN0/XL2_45") (pintype "bidirectional"))
    )
    (net (code "103") (name "unconnected-(U5-P27{slash}AIN1{slash}XL1-Pad46)") (class "Default")
      (node (ref "U5") (pin "46") (pinfunction "P27/AIN1/XL1_46") (pintype "bidirectional"))
    )
    (net (code "104") (name "unconnected-(U5-P28-Pad47)") (class "Default")
      (node (ref "U5") (pin "47") (pinfunction "P28_47") (pintype "bidirectional"))
    )
    (net (code "105") (name "unconnected-(U5-P29-Pad48)") (class "Default")
      (node (ref "U5") (pin "48") (pinfunction "P29_48") (pintype "bidirectional"))
    )
    (net (code "106") (name "unconnected-(U5-P30-Pad3)") (class "Default")
      (node (ref "U5") (pin "3") (pinfunction "P30_3") (pintype "bidirectional"))
    )
    (net (code "107") (name "unconnected-(U6-PA10-Pad30)") (class "Default")
      (node (ref "U6") (pin "30") (pinfunction "PA10_30") (pintype "bidirectional"))
    )
    (net (code "108") (name "unconnected-(U6-PA19-Pad50)") (class "Default")
      (node (ref "U6") (pin "50") (pinfunction "PA19_50") (pintype "bidirectional"))
    )
    (net (code "109") (name "unconnected-(U6-PB13-Pad54)") (class "Default")
      (node (ref "U6") (pin "54") (pinfunction "PB13_54") (pintype "bidirectional"))
    )
    (net (code "110") (name "unconnected-(U6-XIN32-Pad17)") (class "Default")
      (node (ref "U6") (pin "17") (pinfunction "XIN32_17") (pintype "bidirectional"))
    )
    (net (code "111") (name "unconnected-(U6-XOUT32-Pad18)") (class "Default")
      (node (ref "U6") (pin "18") (pinfunction "XOUT32_18") (pintype "bidirectional"))
    )
    (net (code "112") (name "~{FTDI_RTS}") (class "Default")
      (node (ref "TP11") (pin "TP") (pinfunction "TP_TP") (pintype "input"))
      (node (ref "U1") (pin "19") (pinfunction "~{RTS}_19") (pintype "bidirectional"))
      (node (ref "U6") (pin "26") (pinfunction "PA08_26") (pintype "bidirectional"))
    )
    (net (code "113") (name "~{LIGHT_INT}") (class "Default")
      (node (ref "R8") (pin "1") (pinfunction "1_1") (pintype "passive"))
      (node (ref "TP10") (pin "TP") (pinfunction "TP_TP") (pintype "input"))
      (node (ref "U3") (pin "4") (pinfunction "~{INT}_4") (pintype "bidirectional"))
      (node (ref "U6") (pin "51") (pinfunction "PA20_51") (pintype "bidirectional"))
    )
    (net (code "114") (name "~{NRF_RESET}") (class "Default")
      (node (ref "J3") (pin "2") (pinfunction "SWDIO_2") (pintype "bidirectional"))
      (node (ref "U5") (pin "23") (pinfunction "SWDIO/~{RESET}_23") (pintype "bidirectional"))
      (node (ref "U6") (pin "44") (pinfunction "PA17_44") (pintype "bidirectional"))
    )
    (net (code "115") (name "~{SAM4L_RESET}") (class "Default")
      (node (ref "J2") (pin "3") (pinfunction "~{RESET}_3") (pintype "bidirectional"))
      (node (ref "JP4") (pin "11") (pinfunction "11_11") (pintype "passive"))
      (node (ref "S1") (pin "1") (pinfunction "P$1_1") (pintype "passive"))
      (node (ref "U1") (pin "18") (pinfunction "~{DTR}_18") (pintype "bidirectional"))
      (node (ref "U6") (pin "4") (pinfunction "~{RESET}_4") (pintype "bidirectional"))
    )
  )
)
